# LowLevelv3_1.net
KiCad netlist of a schematic drawn in EAGLE
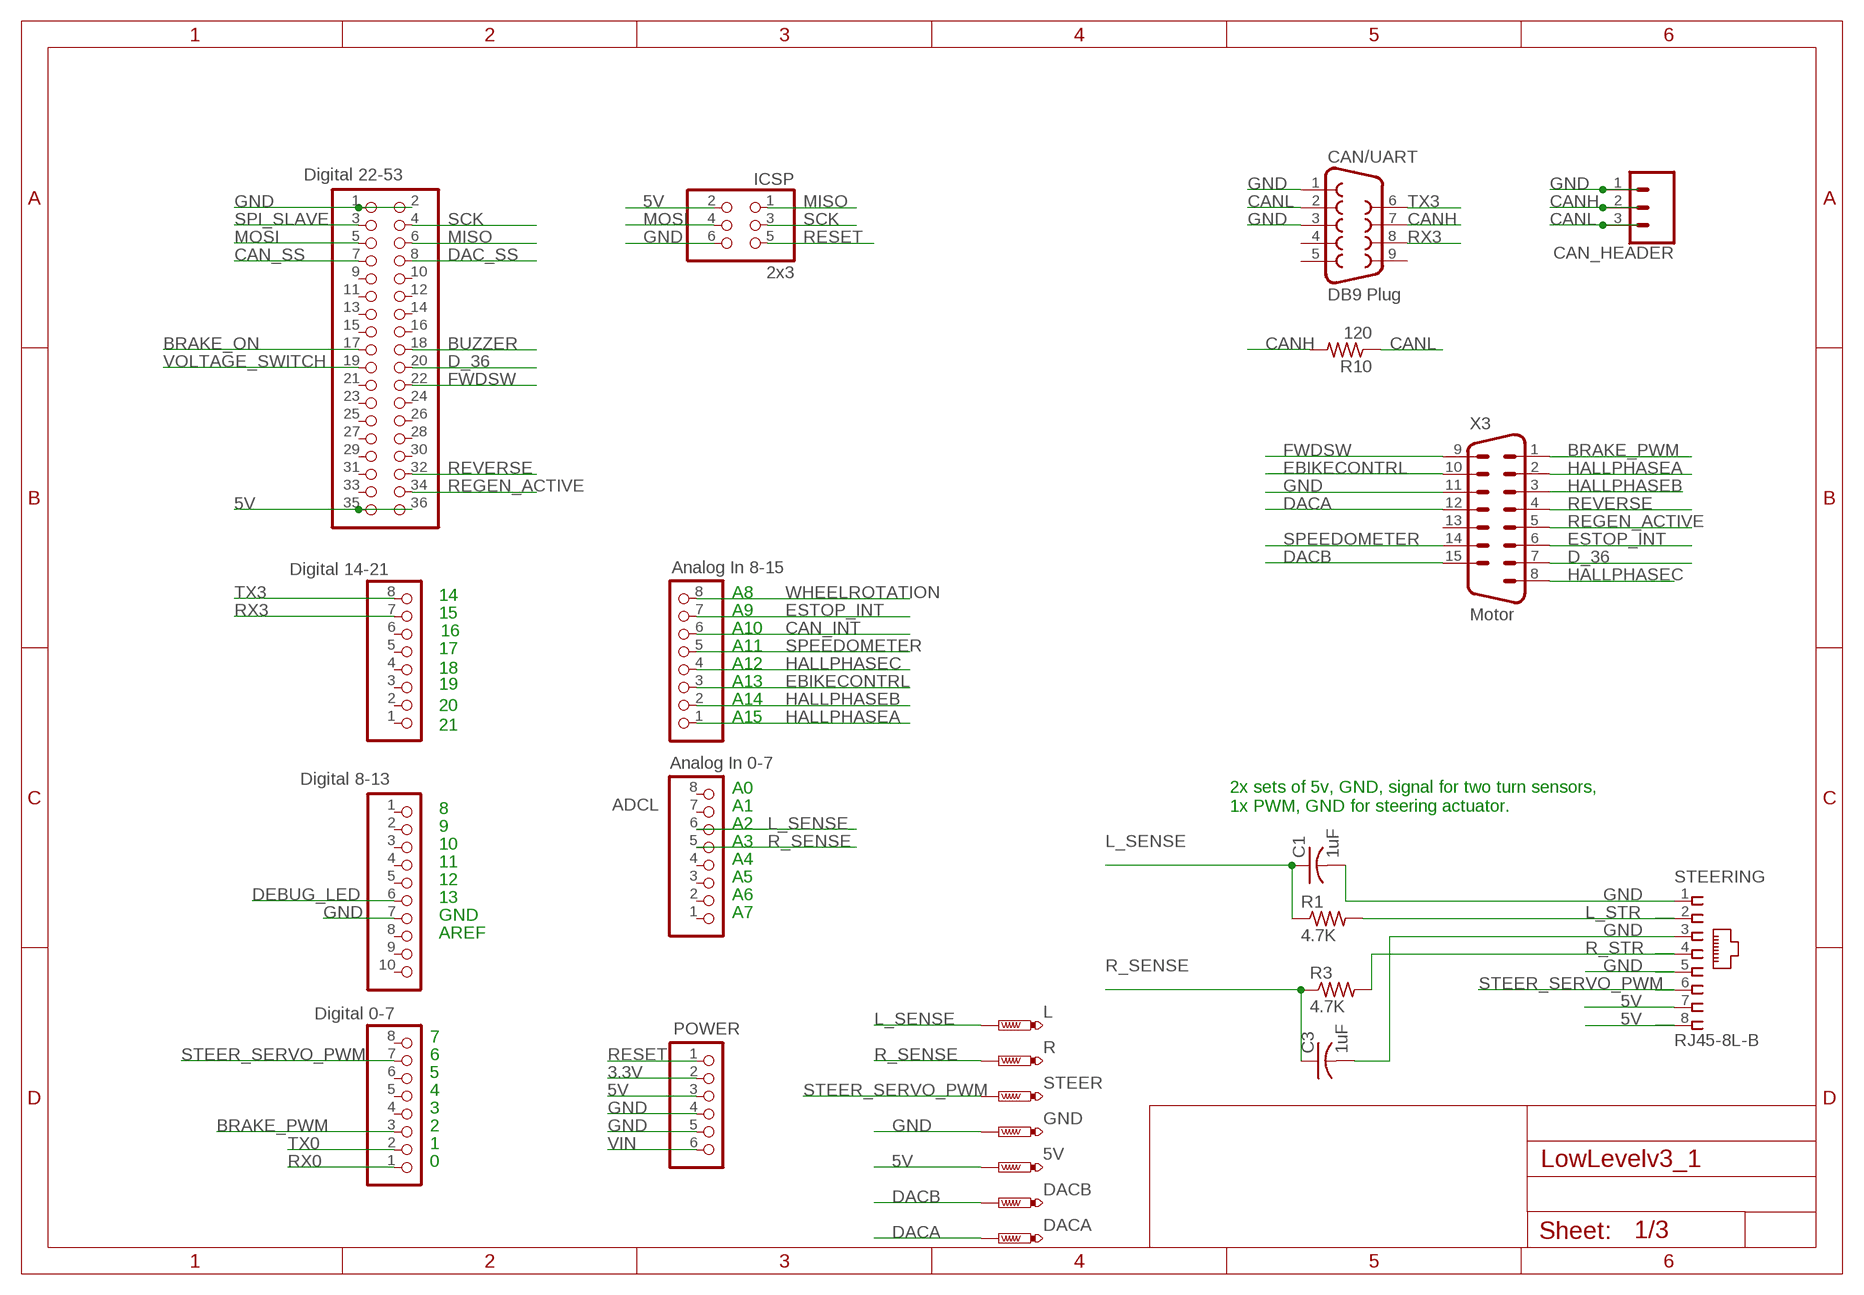
[diagram p0: schematic, sheet 1]
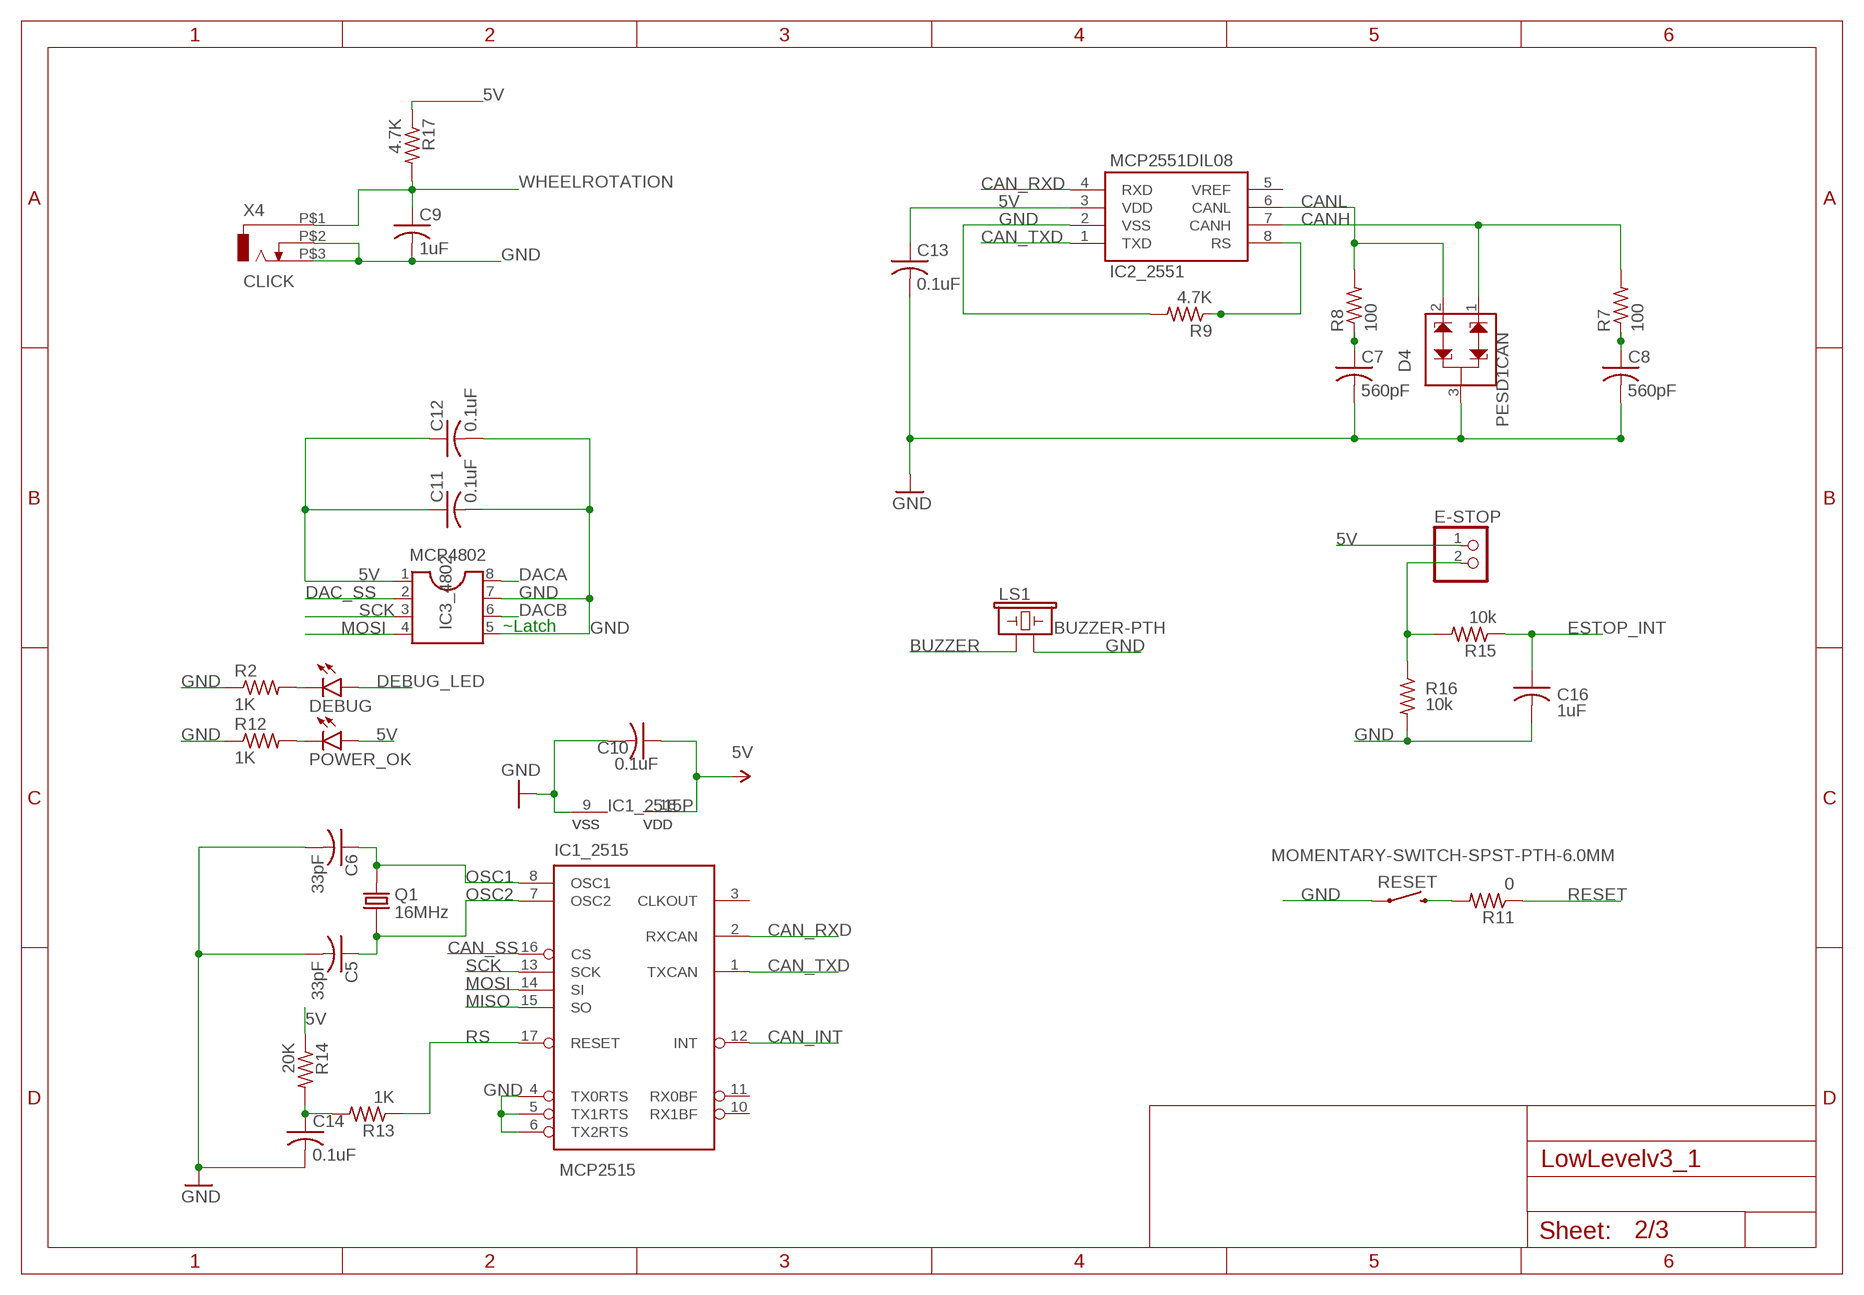
[diagram p1: schematic, sheet 2]
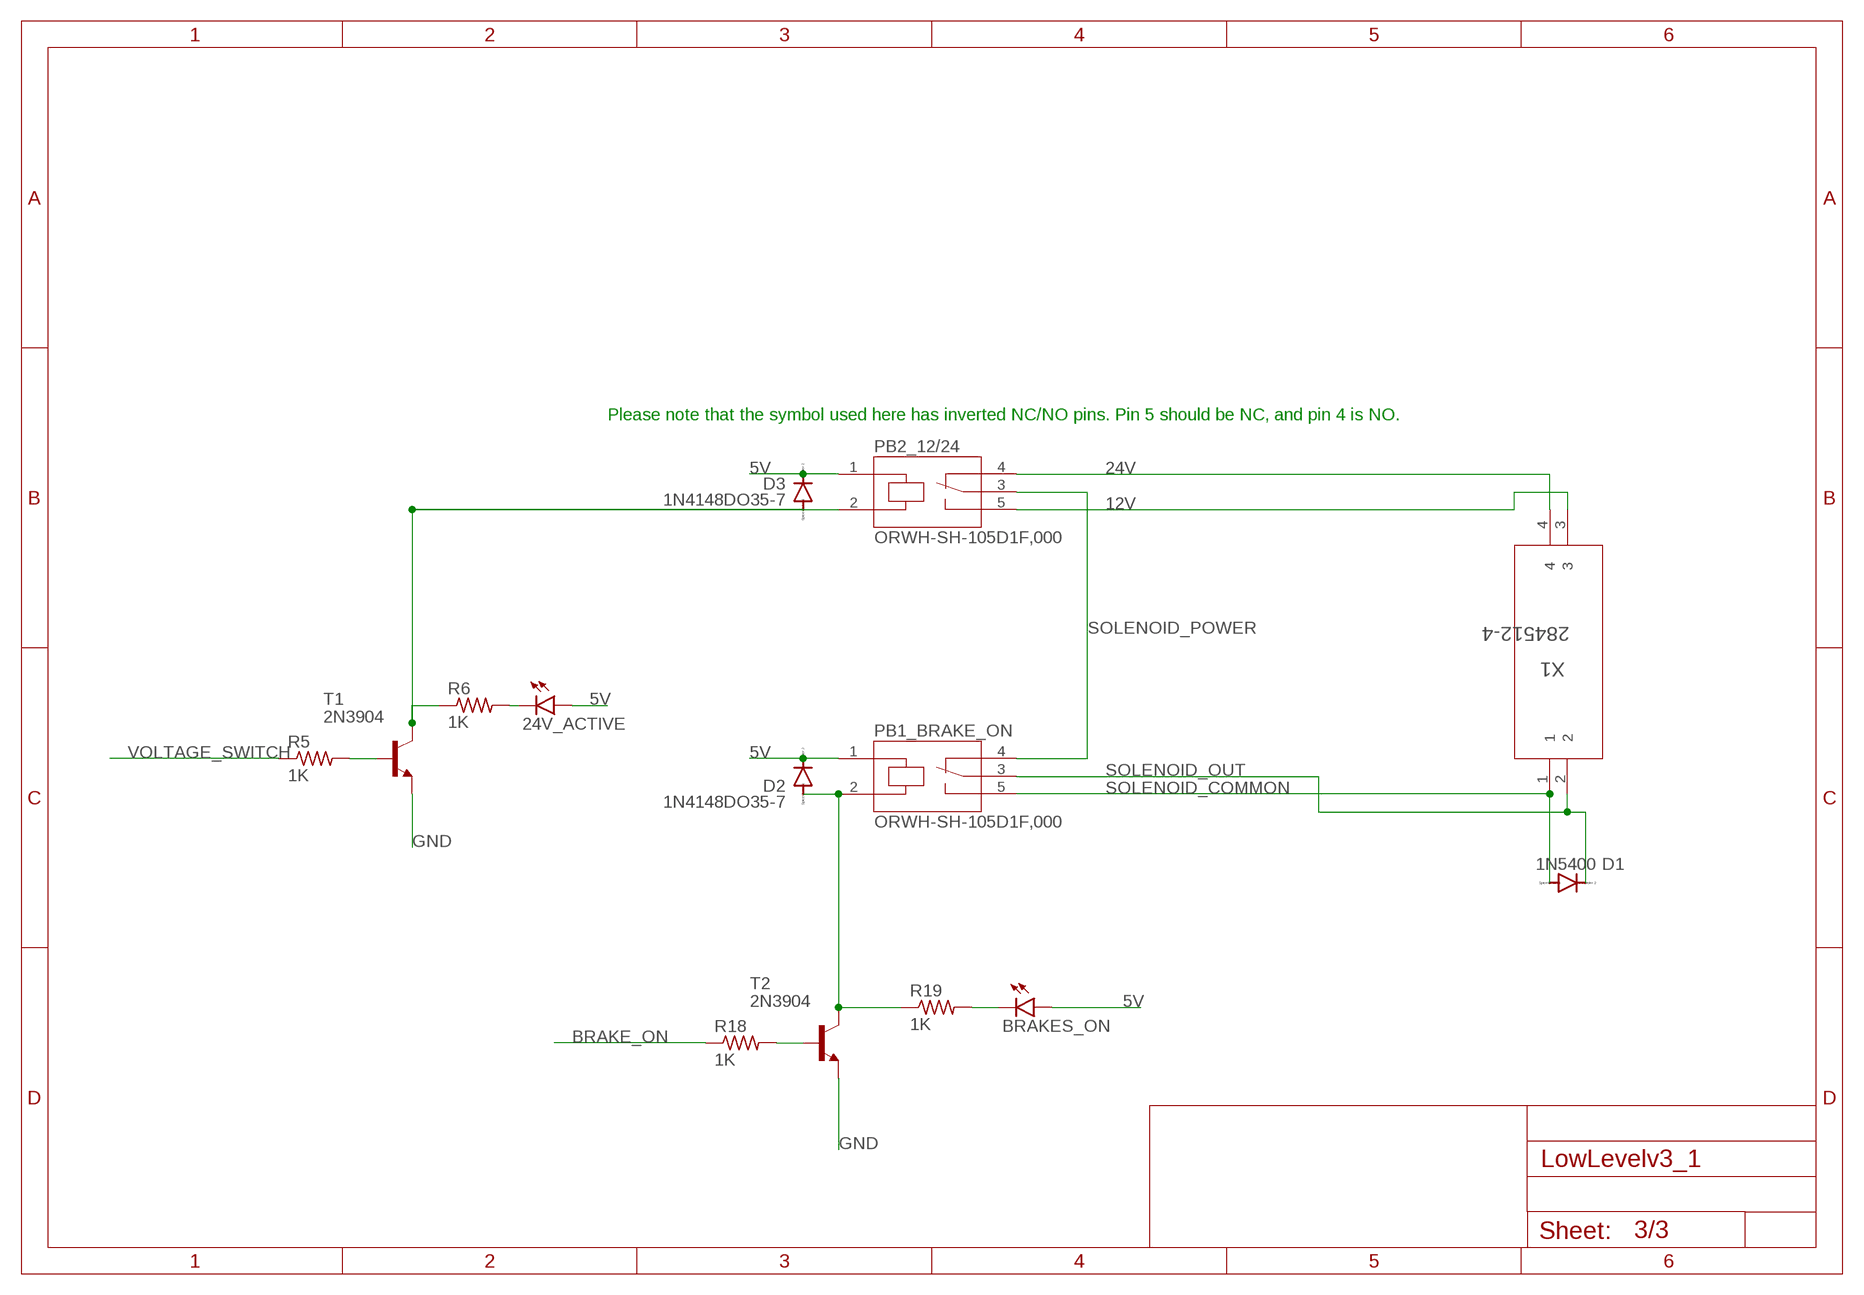
[diagram p2: schematic, sheet 3]

(export (version "E")
  (design (tool "Eeschema 10.0.6"))
  (components
    (comp (ref "5V")
      (value "PTR1PAD1-17")
      (footprint "eagle-import:P1-17")
      (libsource (lib "eagle-import") (part "PTR1PAD1-17"))
    )
    (comp (ref "ADCH")
      (value "Analog In 8-15")
      (footprint "eagle-import:1X08")
      (libsource (lib "eagle-import") (part "PINHD-1X8"))
    )
    (comp (ref "ADCL")
      (value "Analog In 0-7")
      (footprint "eagle-import:1X08")
      (libsource (lib "eagle-import") (part "PINHD-1X8"))
    )
    (comp (ref "C1")
      (value "1uF")
      (footprint "eagle-import:C1206")
      (libsource (lib "eagle-import") (part "C-USC1206"))
    )
    (comp (ref "C3")
      (value "1uF")
      (footprint "eagle-import:C1206")
      (libsource (lib "eagle-import") (part "C-USC1206"))
    )
    (comp (ref "CAN/UART")
      (value "DB9 Plug")
      (footprint "eagle-import:DB9")
      (fields (field (name "SPICEPREFIX") "X"))
      (libsource (lib "eagle-import") (part "DB9FEMALE"))
    )
    (comp (ref "CAN_HEADER")
      (value "CONN_03-SCREW-5MM")
      (footprint "eagle-import:SCREWTERMINAL-5MM-3")
      (libsource (lib "eagle-import") (part "CONN_03-SCREW-5MM"))
    )
    (comp (ref "DACA")
      (value "PTR1PAD1-17")
      (footprint "eagle-import:P1-17")
      (libsource (lib "eagle-import") (part "PTR1PAD1-17"))
    )
    (comp (ref "DACB")
      (value "PTR1PAD1-17")
      (footprint "eagle-import:P1-17")
      (libsource (lib "eagle-import") (part "PTR1PAD1-17"))
    )
    (comp (ref "DIGITAL_0-7")
      (value "Digital 0-7")
      (footprint "eagle-import:1X08")
      (libsource (lib "eagle-import") (part "PINHD-1X8"))
    )
    (comp (ref "DIGITAL_8-13")
      (value "Digital 8-13")
      (footprint "eagle-import:1X10")
      (libsource (lib "eagle-import") (part "PINHD-1X10"))
    )
    (comp (ref "DIGITAL_14-21")
      (value "Digital 14-21")
      (footprint "eagle-import:1X08")
      (libsource (lib "eagle-import") (part "PINHD-1X8"))
    )
    (comp (ref "GND")
      (value "PTR1PAD1-17")
      (footprint "eagle-import:P1-17")
      (libsource (lib "eagle-import") (part "PTR1PAD1-17"))
    )
    (comp (ref "ICSP")
      (value "2x3")
      (footprint "eagle-import:2X03")
      (libsource (lib "eagle-import") (part "PINHD-2X3"))
    )
    (comp (ref "L")
      (value "PTR1PAD1-17")
      (footprint "eagle-import:P1-17")
      (libsource (lib "eagle-import") (part "PTR1PAD1-17"))
    )
    (comp (ref "MEGA_EXPANSION")
      (value "Digital 22-53")
      (footprint "eagle-import:PINHEAD_2X18")
      (libsource (lib "eagle-import") (part "PINHEAD_PINHD-2X18"))
    )
    (comp (ref "POWER")
      (value "PINHD-1X6")
      (footprint "eagle-import:1X06")
      (libsource (lib "eagle-import") (part "PINHD-1X6"))
    )
    (comp (ref "R")
      (value "PTR1PAD1-17")
      (footprint "eagle-import:P1-17")
      (libsource (lib "eagle-import") (part "PTR1PAD1-17"))
    )
    (comp (ref "R1")
      (value "4.7K")
      (footprint "eagle-import:R1206")
      (libsource (lib "eagle-import") (part "R-US_R1206"))
    )
    (comp (ref "R3")
      (value "4.7K")
      (footprint "eagle-import:R1206")
      (libsource (lib "eagle-import") (part "R-US_R1206"))
    )
    (comp (ref "R10")
      (value "120")
      (footprint "eagle-import:R1206")
      (libsource (lib "eagle-import") (part "R-US_R1206"))
    )
    (comp (ref "STEER")
      (value "PTR1PAD1-17")
      (footprint "eagle-import:P1-17")
      (libsource (lib "eagle-import") (part "PTR1PAD1-17"))
    )
    (comp (ref "STEERING")
      (value "RJ45-8L-B")
      (footprint "eagle-import:RJ45-NO-SHIELD")
      (fields (field (name "MF") "TYCO ELECTRONICS"))
      (libsource (lib "eagle-import") (part "RJ45-8L-B"))
    )
    (comp (ref "X3")
      (value "Motor")
      (footprint "eagle-import:182-015-MALE")
      (libsource (lib "eagle-import") (part "M15-182"))
    )
    (comp (ref "24V_ACTIVE")
      (value "LED3MM")
      (footprint "eagle-import:LED3MM")
      (libsource (lib "eagle-import") (part "LED3MM"))
    )
    (comp (ref "BRAKES_ON")
      (value "LED3MM")
      (footprint "eagle-import:LED3MM")
      (libsource (lib "eagle-import") (part "LED3MM"))
    )
    (comp (ref "D1")
      (value "1N5400")
      (footprint "eagle-import:DO201-15")
      (libsource (lib "eagle-import") (part "1N5400"))
    )
    (comp (ref "D2")
      (value "1N4148DO35-7")
      (footprint "eagle-import:DO35-7")
      (libsource (lib "eagle-import") (part "1N4148DO35-7"))
    )
    (comp (ref "D3")
      (value "1N4148DO35-7")
      (footprint "eagle-import:DO35-7")
      (libsource (lib "eagle-import") (part "1N4148DO35-7"))
    )
    (comp (ref "PB1_BRAKE_ON")
      (value "ORWH-SH-105D1F,000")
      (footprint "eagle-import:TE_ORWH-SH-105D1F,000")
      (fields (field (name "DIGI-KEY_PART_NUMBER") "PB2032-ND") (field (name "MF") "TE"))
      (libsource (lib "eagle-import") (part "ORWH-SH-105D1F,000"))
    )
    (comp (ref "PB2_12/24")
      (value "ORWH-SH-105D1F,000")
      (footprint "eagle-import:TE_ORWH-SH-105D1F,000")
      (fields (field (name "DIGI-KEY_PART_NUMBER") "PB2032-ND") (field (name "MF") "TE"))
      (libsource (lib "eagle-import") (part "ORWH-SH-105D1F,000"))
    )
    (comp (ref "R5")
      (value "1K")
      (footprint "eagle-import:R1206")
      (libsource (lib "eagle-import") (part "R-US_R1206"))
    )
    (comp (ref "R6")
      (value "1K")
      (footprint "eagle-import:R1206")
      (libsource (lib "eagle-import") (part "R-US_R1206"))
    )
    (comp (ref "R18")
      (value "1K")
      (footprint "eagle-import:R1206")
      (libsource (lib "eagle-import") (part "R-US_R1206"))
    )
    (comp (ref "R19")
      (value "1K")
      (footprint "eagle-import:R1206")
      (libsource (lib "eagle-import") (part "R-US_R1206"))
    )
    (comp (ref "T1")
      (value "2N3904")
      (footprint "eagle-import:TO92")
      (libsource (lib "eagle-import") (part "2N3904"))
    )
    (comp (ref "T2")
      (value "2N3904")
      (footprint "eagle-import:TO92")
      (libsource (lib "eagle-import") (part "2N3904"))
    )
    (comp (ref "X1")
      (value "284512-4")
      (footprint "eagle-import:284512-4")
      (fields (field (name "MANUFACTURER_PART_NUMBER") "2845124"))
      (libsource (lib "eagle-import") (part "284512-4"))
    )
    (comp (ref "C5")
      (value "33pF")
      (footprint "eagle-import:C1206")
      (libsource (lib "eagle-import") (part "C-USC1206"))
    )
    (comp (ref "C6")
      (value "33pF")
      (footprint "eagle-import:C1206")
      (libsource (lib "eagle-import") (part "C-USC1206"))
    )
    (comp (ref "C7")
      (value "560pF")
      (footprint "eagle-import:C1206")
      (libsource (lib "eagle-import") (part "C-USC1206"))
    )
    (comp (ref "C8")
      (value "560pF")
      (footprint "eagle-import:C1206")
      (libsource (lib "eagle-import") (part "C-USC1206"))
    )
    (comp (ref "C9")
      (value "1uF")
      (footprint "eagle-import:C1206")
      (libsource (lib "eagle-import") (part "C-USC1206"))
    )
    (comp (ref "C10")
      (value "0.1uF")
      (footprint "eagle-import:C1206")
      (libsource (lib "eagle-import") (part "C-USC1206"))
    )
    (comp (ref "C11")
      (value "0.1uF")
      (footprint "eagle-import:C1206")
      (libsource (lib "eagle-import") (part "C-USC1206"))
    )
    (comp (ref "C12")
      (value "0.1uF")
      (footprint "eagle-import:C1206")
      (libsource (lib "eagle-import") (part "C-USC1206"))
    )
    (comp (ref "C13")
      (value "0.1uF")
      (footprint "eagle-import:C1206")
      (libsource (lib "eagle-import") (part "C-USC1206"))
    )
    (comp (ref "C14")
      (value "0.1uF")
      (footprint "eagle-import:C1206")
      (libsource (lib "eagle-import") (part "C-USC1206"))
    )
    (comp (ref "C16")
      (value "1uF")
      (footprint "eagle-import:C1206")
      (libsource (lib "eagle-import") (part "C-USC1206"))
    )
    (comp (ref "D4")
      (value "PESD1CAN")
      (footprint "eagle-import:SPARKFUN-DISCRETESEMI_SOT23-3")
      (fields (field (name "SPICEPREFIX") "J"))
      (libsource (lib "eagle-import") (part "PESD1CAN"))
    )
    (comp (ref "DEBUG")
      (value "LED3MM")
      (footprint "eagle-import:LED3MM")
      (libsource (lib "eagle-import") (part "LED3MM"))
    )
    (comp (ref "E-STOP")
      (value "PINHD-1X2")
      (footprint "eagle-import:1X02")
      (libsource (lib "eagle-import") (part "PINHD-1X2"))
    )
    (comp (ref "IC1_2515")
      (value "MCP2515")
      (footprint "eagle-import:DIP18")
      (fields (field (name "SPICEPREFIX") "X"))
      (libsource (lib "eagle-import") (part "MCP2515(MCP2510)P"))
    )
    (comp (ref "IC2_2551")
      (value "MCP2551DIL08")
      (footprint "eagle-import:IC-PACKAGE_DIL08")
      (fields (field (name "SPICEPREFIX") "X"))
      (libsource (lib "eagle-import") (part "MCP2551DIL08"))
    )
    (comp (ref "IC3_4802")
      (value "MCP4802")
      (footprint "eagle-import:DIL08")
      (libsource (lib "eagle-import") (part "DIL8"))
    )
    (comp (ref "LS1")
      (value "BUZZER-PTH")
      (footprint "eagle-import:BUZZER-12MM")
      (libsource (lib "eagle-import") (part "BUZZER-PTH"))
    )
    (comp (ref "POWER_OK")
      (value "LED3MM")
      (footprint "eagle-import:LED3MM")
      (libsource (lib "eagle-import") (part "LED3MM"))
    )
    (comp (ref "Q1")
      (value "16MHz")
      (footprint "eagle-import:XTAL_ECS-160-20-46X")
      (fields
        (field (name "DIGI-KEY_PART_NUMBER") "XC1759-ND")
        (field (name "MF") "ECS Inc.")
        (field (name "MP") "ECS-160-20-46X")
        (field (name "SPICEPREFIX") "B")
      )
      (libsource (lib "eagle-import") (part "ECS-160-20-46X"))
    )
    (comp (ref "R2")
      (value "1K")
      (footprint "eagle-import:R1206")
      (libsource (lib "eagle-import") (part "R-US_R1206"))
    )
    (comp (ref "R7")
      (value "100")
      (footprint "eagle-import:R1206")
      (libsource (lib "eagle-import") (part "R-US_R1206"))
    )
    (comp (ref "R8")
      (value "100")
      (footprint "eagle-import:R1206")
      (libsource (lib "eagle-import") (part "R-US_R1206"))
    )
    (comp (ref "R9")
      (value "4.7K")
      (footprint "eagle-import:R1206")
      (libsource (lib "eagle-import") (part "R-US_R1206"))
    )
    (comp (ref "R11")
      (value "0")
      (footprint "eagle-import:R1206")
      (libsource (lib "eagle-import") (part "R-US_R1206"))
    )
    (comp (ref "R12")
      (value "1K")
      (footprint "eagle-import:R1206")
      (libsource (lib "eagle-import") (part "R-US_R1206"))
    )
    (comp (ref "R13")
      (value "1K")
      (footprint "eagle-import:R1206")
      (libsource (lib "eagle-import") (part "R-US_R1206"))
    )
    (comp (ref "R14")
      (value "20K")
      (footprint "eagle-import:R1206")
      (libsource (lib "eagle-import") (part "R-US_R1206"))
    )
    (comp (ref "R15")
      (value "10k")
      (footprint "eagle-import:R1206")
      (libsource (lib "eagle-import") (part "R-US_R1206"))
    )
    (comp (ref "R16")
      (value "10k")
      (footprint "eagle-import:R1206")
      (libsource (lib "eagle-import") (part "R-US_R1206"))
    )
    (comp (ref "R17")
      (value "4.7K")
      (footprint "eagle-import:R1206")
      (libsource (lib "eagle-import") (part "R-US_R1206"))
    )
    (comp (ref "RESET")
      (value "MOMENTARY-SWITCH-SPST-PTH-6.0MM")
      (footprint "eagle-import:TACTILE_SWITCH_PTH_6.0MM")
      (libsource (lib "eagle-import") (part "MOMENTARY-SWITCH-SPST-PTH-6.0MM"))
    )
    (comp (ref "X4")
      (value "CLICK")
      (footprint "eagle-import:ODO_JACK")
      (libsource (lib "eagle-import") (part "ODO_JACK"))
    )
  )
  (nets
    (net (code "1") (name "3.3V") (class "Default")
      (node (ref "POWER") (pin "2") (pinfunction "2_2") (pintype "passive"))
    )
    (net (code "2") (name "5V") (class "Default")
      (node (ref "24V_ACTIVE") (pin "A") (pinfunction "A_A") (pintype "passive"))
      (node (ref "5V") (pin "TP") (pinfunction "TP_TP") (pintype "input"))
      (node (ref "BRAKES_ON") (pin "A") (pinfunction "A_A") (pintype "passive"))
      (node (ref "C10") (pin "1") (pinfunction "1_1") (pintype "passive"))
      (node (ref "C11") (pin "1") (pinfunction "1_1") (pintype "passive"))
      (node (ref "C12") (pin "1") (pinfunction "1_1") (pintype "passive"))
      (node (ref "C13") (pin "1") (pinfunction "1_1") (pintype "passive"))
      (node (ref "D2") (pin "C") (pinfunction "C_C") (pintype "passive"))
      (node (ref "D3") (pin "C") (pinfunction "C_C") (pintype "passive"))
      (node (ref "E-STOP") (pin "1") (pinfunction "1_1") (pintype "passive"))
      (node (ref "IC1_2515") (pin "18") (pinfunction "VDD_18") (pintype "power_in"))
      (node (ref "IC2_2551") (pin "3") (pinfunction "VDD_3") (pintype "bidirectional"))
      (node (ref "IC3_4802") (pin "1") (pinfunction "1_1") (pintype "passive"))
      (node (ref "ICSP") (pin "2") (pinfunction "2_2") (pintype "passive"))
      (node (ref "MEGA_EXPANSION") (pin "35") (pinfunction "35_35") (pintype "passive"))
      (node (ref "MEGA_EXPANSION") (pin "36") (pinfunction "36_36") (pintype "passive"))
      (node (ref "PB1_BRAKE_ON") (pin "1") (pinfunction "C1_1") (pintype "passive"))
      (node (ref "PB2_12/24") (pin "1") (pinfunction "C1_1") (pintype "passive"))
      (node (ref "POWER") (pin "3") (pinfunction "3_3") (pintype "passive"))
      (node (ref "POWER_OK") (pin "A") (pinfunction "A_A") (pintype "passive"))
      (node (ref "R14") (pin "1") (pinfunction "1_1") (pintype "passive"))
      (node (ref "R17") (pin "1") (pinfunction "1_1") (pintype "passive"))
      (node (ref "STEERING") (pin "7") (pinfunction "7_7") (pintype "passive"))
      (node (ref "STEERING") (pin "8") (pinfunction "8_8") (pintype "passive"))
    )
    (net (code "3") (name "12V") (class "Default")
      (node (ref "PB2_12/24") (pin "5") (pinfunction "NO_5") (pintype "passive"))
      (node (ref "X1") (pin "3") (pinfunction "3_3") (pintype "passive"))
    )
    (net (code "4") (name "24V") (class "Default")
      (node (ref "PB2_12/24") (pin "4") (pinfunction "NC_4") (pintype "passive"))
      (node (ref "X1") (pin "4") (pinfunction "4_4") (pintype "passive"))
    )
    (net (code "5") (name "BRAKE_ON") (class "Default")
      (node (ref "MEGA_EXPANSION") (pin "17") (pinfunction "17_17") (pintype "passive"))
      (node (ref "R18") (pin "1") (pinfunction "1_1") (pintype "passive"))
    )
    (net (code "6") (name "BRAKE_PWM") (class "Default")
      (node (ref "DIGITAL_0-7") (pin "3") (pinfunction "3_3") (pintype "passive"))
      (node (ref "X3") (pin "1") (pinfunction "1_1") (pintype "passive"))
    )
    (net (code "7") (name "BUZZER") (class "Default")
      (node (ref "LS1") (pin "+") (pinfunction "1_+") (pintype "passive"))
      (node (ref "MEGA_EXPANSION") (pin "18") (pinfunction "18_18") (pintype "passive"))
    )
    (net (code "8") (name "CANH") (class "Default")
      (node (ref "CAN/UART") (pin "7") (pinfunction "7_7") (pintype "passive"))
      (node (ref "CAN_HEADER") (pin "2") (pinfunction "2_2") (pintype "passive"))
      (node (ref "D4") (pin "1") (pinfunction "1_1") (pintype "bidirectional"))
      (node (ref "IC2_2551") (pin "7") (pinfunction "CANH_7") (pintype "bidirectional"))
      (node (ref "R10") (pin "2") (pinfunction "2_2") (pintype "passive"))
      (node (ref "R7") (pin "2") (pinfunction "2_2") (pintype "passive"))
    )
    (net (code "9") (name "CANL") (class "Default")
      (node (ref "CAN/UART") (pin "2") (pinfunction "2_2") (pintype "passive"))
      (node (ref "CAN_HEADER") (pin "3") (pinfunction "3_3") (pintype "passive"))
      (node (ref "D4") (pin "2") (pinfunction "2_2") (pintype "bidirectional"))
      (node (ref "IC2_2551") (pin "6") (pinfunction "CANL_6") (pintype "bidirectional"))
      (node (ref "R10") (pin "1") (pinfunction "1_1") (pintype "passive"))
      (node (ref "R8") (pin "2") (pinfunction "2_2") (pintype "passive"))
    )
    (net (code "10") (name "CAN_INT") (class "Default")
      (node (ref "ADCH") (pin "6") (pinfunction "6_6") (pintype "passive"))
      (node (ref "IC1_2515") (pin "12") (pinfunction "INT_12") (pintype "output"))
    )
    (net (code "11") (name "CAN_RXD") (class "Default")
      (node (ref "IC1_2515") (pin "2") (pinfunction "RXCAN_2") (pintype "input"))
      (node (ref "IC2_2551") (pin "4") (pinfunction "RXD_4") (pintype "bidirectional"))
    )
    (net (code "12") (name "CAN_SS") (class "Default")
      (node (ref "IC1_2515") (pin "16") (pinfunction "CS_16") (pintype "input"))
      (node (ref "MEGA_EXPANSION") (pin "7") (pinfunction "7_7") (pintype "passive"))
    )
    (net (code "13") (name "CAN_TXD") (class "Default")
      (node (ref "IC1_2515") (pin "1") (pinfunction "TXCAN_1") (pintype "output"))
      (node (ref "IC2_2551") (pin "1") (pinfunction "TXD_1") (pintype "bidirectional"))
    )
    (net (code "14") (name "DACA") (class "Default")
      (node (ref "DACA") (pin "TP") (pinfunction "TP_TP") (pintype "input"))
      (node (ref "IC3_4802") (pin "8") (pinfunction "8_8") (pintype "passive"))
      (node (ref "X3") (pin "12") (pinfunction "12_12") (pintype "passive"))
    )
    (net (code "15") (name "DACB") (class "Default")
      (node (ref "DACB") (pin "TP") (pinfunction "TP_TP") (pintype "input"))
      (node (ref "IC3_4802") (pin "6") (pinfunction "6_6") (pintype "passive"))
      (node (ref "X3") (pin "15") (pinfunction "15_15") (pintype "passive"))
    )
    (net (code "16") (name "DAC_SS") (class "Default")
      (node (ref "IC3_4802") (pin "2") (pinfunction "2_2") (pintype "passive"))
      (node (ref "MEGA_EXPANSION") (pin "8") (pinfunction "8_8") (pintype "passive"))
    )
    (net (code "17") (name "DEBUG_LED") (class "Default")
      (node (ref "DEBUG") (pin "A") (pinfunction "A_A") (pintype "passive"))
      (node (ref "DIGITAL_8-13") (pin "6") (pinfunction "6_6") (pintype "passive"))
    )
    (net (code "18") (name "D_36") (class "Default")
      (node (ref "MEGA_EXPANSION") (pin "20") (pinfunction "20_20") (pintype "passive"))
      (node (ref "X3") (pin "7") (pinfunction "7_7") (pintype "passive"))
    )
    (net (code "19") (name "EBIKECONTRL") (class "Default")
      (node (ref "ADCH") (pin "3") (pinfunction "3_3") (pintype "passive"))
      (node (ref "X3") (pin "10") (pinfunction "10_10") (pintype "passive"))
    )
    (net (code "20") (name "ESTOP_INT") (class "Default")
      (node (ref "ADCH") (pin "7") (pinfunction "7_7") (pintype "passive"))
      (node (ref "C16") (pin "1") (pinfunction "1_1") (pintype "passive"))
      (node (ref "R15") (pin "1") (pinfunction "1_1") (pintype "passive"))
      (node (ref "X3") (pin "6") (pinfunction "6_6") (pintype "passive"))
    )
    (net (code "21") (name "FWDSW") (class "Default")
      (node (ref "MEGA_EXPANSION") (pin "22") (pinfunction "22_22") (pintype "passive"))
      (node (ref "X3") (pin "9") (pinfunction "9_9") (pintype "passive"))
    )
    (net (code "22") (name "GND") (class "Default")
      (node (ref "C1") (pin "2") (pinfunction "2_2") (pintype "passive"))
      (node (ref "C10") (pin "2") (pinfunction "2_2") (pintype "passive"))
      (node (ref "C11") (pin "2") (pinfunction "2_2") (pintype "passive"))
      (node (ref "C12") (pin "2") (pinfunction "2_2") (pintype "passive"))
      (node (ref "C13") (pin "2") (pinfunction "2_2") (pintype "passive"))
      (node (ref "C14") (pin "2") (pinfunction "2_2") (pintype "passive"))
      (node (ref "C16") (pin "2") (pinfunction "2_2") (pintype "passive"))
      (node (ref "C3") (pin "2") (pinfunction "2_2") (pintype "passive"))
      (node (ref "C5") (pin "2") (pinfunction "2_2") (pintype "passive"))
      (node (ref "C6") (pin "2") (pinfunction "2_2") (pintype "passive"))
      (node (ref "C7") (pin "2") (pinfunction "2_2") (pintype "passive"))
      (node (ref "C8") (pin "2") (pinfunction "2_2") (pintype "passive"))
      (node (ref "C9") (pin "2") (pinfunction "2_2") (pintype "passive"))
      (node (ref "CAN/UART") (pin "1") (pinfunction "1_1") (pintype "passive"))
      (node (ref "CAN/UART") (pin "3") (pinfunction "3_3") (pintype "passive"))
      (node (ref "CAN_HEADER") (pin "1") (pinfunction "1_1") (pintype "passive"))
      (node (ref "D4") (pin "3") (pinfunction "3_3") (pintype "bidirectional"))
      (node (ref "DIGITAL_8-13") (pin "7") (pinfunction "7_7") (pintype "passive"))
      (node (ref "GND") (pin "TP") (pinfunction "TP_TP") (pintype "input"))
      (node (ref "IC1_2515") (pin "4") (pinfunction "TX0RTS_4") (pintype "input"))
      (node (ref "IC1_2515") (pin "5") (pinfunction "TX1RTS_5") (pintype "input"))
      (node (ref "IC1_2515") (pin "6") (pinfunction "TX2RTS_6") (pintype "input"))
      (node (ref "IC1_2515") (pin "9") (pinfunction "VSS_9") (pintype "power_in"))
      (node (ref "IC2_2551") (pin "2") (pinfunction "VSS_2") (pintype "bidirectional"))
      (node (ref "IC3_4802") (pin "5") (pinfunction "5_5") (pintype "passive"))
      (node (ref "IC3_4802") (pin "7") (pinfunction "7_7") (pintype "passive"))
      (node (ref "ICSP") (pin "6") (pinfunction "6_6") (pintype "passive"))
      (node (ref "LS1") (pin "-") (pinfunction "2_-") (pintype "passive"))
      (node (ref "MEGA_EXPANSION") (pin "1") (pinfunction "1_1") (pintype "passive"))
      (node (ref "MEGA_EXPANSION") (pin "2") (pinfunction "2_2") (pintype "passive"))
      (node (ref "POWER") (pin "4") (pinfunction "4_4") (pintype "passive"))
      (node (ref "POWER") (pin "5") (pinfunction "5_5") (pintype "passive"))
      (node (ref "R12") (pin "1") (pinfunction "1_1") (pintype "passive"))
      (node (ref "R16") (pin "2") (pinfunction "2_2") (pintype "passive"))
      (node (ref "R2") (pin "1") (pinfunction "1_1") (pintype "passive"))
      (node (ref "R9") (pin "2") (pinfunction "2_2") (pintype "passive"))
      (node (ref "RESET") (pin "1") (pinfunction "1_1") (pintype "passive"))
      (node (ref "STEERING") (pin "1") (pinfunction "1_1") (pintype "passive"))
      (node (ref "STEERING") (pin "3") (pinfunction "3_3") (pintype "passive"))
      (node (ref "STEERING") (pin "5") (pinfunction "5_5") (pintype "passive"))
      (node (ref "T1") (pin "3") (pinfunction "E_3") (pintype "passive"))
      (node (ref "T2") (pin "3") (pinfunction "E_3") (pintype "passive"))
      (node (ref "X3") (pin "11") (pinfunction "11_11") (pintype "passive"))
      (node (ref "X4") (pin "P$2") (pinfunction "2_P$2") (pintype "passive"))
      (node (ref "X4") (pin "P$3") (pinfunction "3_P$3") (pintype "passive"))
    )
    (net (code "23") (name "HALLPHASEA") (class "Default")
      (node (ref "ADCH") (pin "1") (pinfunction "1_1") (pintype "passive"))
      (node (ref "X3") (pin "2") (pinfunction "2_2") (pintype "passive"))
    )
    (net (code "24") (name "HALLPHASEB") (class "Default")
      (node (ref "ADCH") (pin "2") (pinfunction "2_2") (pintype "passive"))
      (node (ref "X3") (pin "3") (pinfunction "3_3") (pintype "passive"))
    )
    (net (code "25") (name "HALLPHASEC") (class "Default")
      (node (ref "ADCH") (pin "4") (pinfunction "4_4") (pintype "passive"))
      (node (ref "X3") (pin "8") (pinfunction "8_8") (pintype "passive"))
    )
    (net (code "26") (name "L_SENSE") (class "Default")
      (node (ref "ADCL") (pin "6") (pinfunction "6_6") (pintype "passive"))
      (node (ref "C1") (pin "1") (pinfunction "1_1") (pintype "passive"))
      (node (ref "L") (pin "TP") (pinfunction "TP_TP") (pintype "input"))
      (node (ref "R1") (pin "1") (pinfunction "1_1") (pintype "passive"))
    )
    (net (code "27") (name "L_STR") (class "Default")
      (node (ref "R1") (pin "2") (pinfunction "2_2") (pintype "passive"))
      (node (ref "STEERING") (pin "2") (pinfunction "2_2") (pintype "passive"))
    )
    (net (code "28") (name "MISO") (class "Default")
      (node (ref "IC1_2515") (pin "15") (pinfunction "SO_15") (pintype "output"))
      (node (ref "ICSP") (pin "1") (pinfunction "1_1") (pintype "passive"))
      (node (ref "MEGA_EXPANSION") (pin "6") (pinfunction "6_6") (pintype "passive"))
    )
    (net (code "29") (name "MOSI") (class "Default")
      (node (ref "IC1_2515") (pin "14") (pinfunction "SI_14") (pintype "input"))
      (node (ref "IC3_4802") (pin "4") (pinfunction "4_4") (pintype "passive"))
      (node (ref "ICSP") (pin "4") (pinfunction "4_4") (pintype "passive"))
      (node (ref "MEGA_EXPANSION") (pin "5") (pinfunction "5_5") (pintype "passive"))
    )
    (net (code "30") (name "Net-(24V_ACTIVE-C)") (class "Default")
      (node (ref "24V_ACTIVE") (pin "K") (pinfunction "C_K") (pintype "passive"))
      (node (ref "R6") (pin "2") (pinfunction "2_2") (pintype "passive"))
    )
    (net (code "31") (name "Net-(BRAKES_ON-C)") (class "Default")
      (node (ref "BRAKES_ON") (pin "K") (pinfunction "C_K") (pintype "passive"))
      (node (ref "R19") (pin "2") (pinfunction "2_2") (pintype "passive"))
    )
    (net (code "32") (name "Net-(C7-Pad1)") (class "Default")
      (node (ref "C7") (pin "1") (pinfunction "1_1") (pintype "passive"))
      (node (ref "R8") (pin "1") (pinfunction "1_1") (pintype "passive"))
    )
    (net (code "33") (name "Net-(C8-Pad1)") (class "Default")
      (node (ref "C8") (pin "1") (pinfunction "1_1") (pintype "passive"))
      (node (ref "R7") (pin "1") (pinfunction "1_1") (pintype "passive"))
    )
    (net (code "34") (name "Net-(C14-Pad1)") (class "Default")
      (node (ref "C14") (pin "1") (pinfunction "1_1") (pintype "passive"))
      (node (ref "R13") (pin "2") (pinfunction "2_2") (pintype "passive"))
      (node (ref "R14") (pin "2") (pinfunction "2_2") (pintype "passive"))
    )
    (net (code "35") (name "Net-(DEBUG-C)") (class "Default")
      (node (ref "DEBUG") (pin "K") (pinfunction "C_K") (pintype "passive"))
      (node (ref "R2") (pin "2") (pinfunction "2_2") (pintype "passive"))
    )
    (net (code "36") (name "Net-(E-STOP-Pad2)") (class "Default")
      (node (ref "E-STOP") (pin "2") (pinfunction "2_2") (pintype "passive"))
      (node (ref "R15") (pin "2") (pinfunction "2_2") (pintype "passive"))
      (node (ref "R16") (pin "1") (pinfunction "1_1") (pintype "passive"))
    )
    (net (code "37") (name "Net-(IC2_2551-RS)") (class "Default")
      (node (ref "IC2_2551") (pin "8") (pinfunction "RS_8") (pintype "bidirectional"))
      (node (ref "R9") (pin "1") (pinfunction "1_1") (pintype "passive"))
    )
    (net (code "38") (name "Net-(PB1_BRAKE_ON-C2)") (class "Default")
      (node (ref "D2") (pin "A") (pinfunction "A_A") (pintype "passive"))
      (node (ref "PB1_BRAKE_ON") (pin "2") (pinfunction "C2_2") (pintype "passive"))
      (node (ref "R19") (pin "1") (pinfunction "1_1") (pintype "passive"))
      (node (ref "T2") (pin "1") (pinfunction "C_1") (pintype "passive"))
    )
    (net (code "39") (name "Net-(PB2_12/24-C2)") (class "Default")
      (node (ref "D3") (pin "A") (pinfunction "A_A") (pintype "passive"))
      (node (ref "PB2_12/24") (pin "2") (pinfunction "C2_2") (pintype "passive"))
      (node (ref "R6") (pin "1") (pinfunction "1_1") (pintype "passive"))
      (node (ref "T1") (pin "1") (pinfunction "C_1") (pintype "passive"))
    )
    (net (code "40") (name "Net-(POWER_OK-C)") (class "Default")
      (node (ref "POWER_OK") (pin "K") (pinfunction "C_K") (pintype "passive"))
      (node (ref "R12") (pin "2") (pinfunction "2_2") (pintype "passive"))
    )
    (net (code "41") (name "Net-(RESET-2)") (class "Default")
      (node (ref "R11") (pin "2") (pinfunction "2_2") (pintype "passive"))
      (node (ref "RESET") (pin "3") (pinfunction "2_3") (pintype "passive"))
    )
    (net (code "42") (name "Net-(T1-B)") (class "Default")
      (node (ref "R5") (pin "2") (pinfunction "2_2") (pintype "passive"))
      (node (ref "T1") (pin "2") (pinfunction "B_2") (pintype "passive"))
    )
    (net (code "43") (name "Net-(T2-B)") (class "Default")
      (node (ref "R18") (pin "2") (pinfunction "2_2") (pintype "passive"))
      (node (ref "T2") (pin "2") (pinfunction "B_2") (pintype "passive"))
    )
    (net (code "44") (name "OSC1") (class "Default")
      (node (ref "C6") (pin "1") (pinfunction "1_1") (pintype "passive"))
      (node (ref "IC1_2515") (pin "8") (pinfunction "OSC1_8") (pintype "input"))
      (node (ref "Q1") (pin "2") (pinfunction "2_2") (pintype "passive"))
    )
    (net (code "45") (name "OSC2") (class "Default")
      (node (ref "C5") (pin "1") (pinfunction "1_1") (pintype "passive"))
      (node (ref "IC1_2515") (pin "7") (pinfunction "OSC2_7") (pintype "output"))
      (node (ref "Q1") (pin "1") (pinfunction "1_1") (pintype "passive"))
    )
    (net (code "46") (name "REGEN_ACTIVE") (class "Default")
      (node (ref "MEGA_EXPANSION") (pin "34") (pinfunction "34_34") (pintype "passive"))
      (node (ref "X3") (pin "5") (pinfunction "5_5") (pintype "passive"))
    )
    (net (code "47") (name "RESET") (class "Default")
      (node (ref "ICSP") (pin "5") (pinfunction "5_5") (pintype "passive"))
      (node (ref "POWER") (pin "1") (pinfunction "1_1") (pintype "passive"))
      (node (ref "R11") (pin "1") (pinfunction "1_1") (pintype "passive"))
    )
    (net (code "48") (name "REVERSE") (class "Default")
      (node (ref "MEGA_EXPANSION") (pin "32") (pinfunction "32_32") (pintype "passive"))
      (node (ref "X3") (pin "4") (pinfunction "4_4") (pintype "passive"))
    )
    (net (code "49") (name "RS") (class "Default")
      (node (ref "IC1_2515") (pin "17") (pinfunction "RESET_17") (pintype "input"))
      (node (ref "R13") (pin "1") (pinfunction "1_1") (pintype "passive"))
    )
    (net (code "50") (name "RX0") (class "Default")
      (node (ref "DIGITAL_0-7") (pin "1") (pinfunction "1_1") (pintype "passive"))
    )
    (net (code "51") (name "RX3") (class "Default")
      (node (ref "CAN/UART") (pin "8") (pinfunction "8_8") (pintype "passive"))
      (node (ref "DIGITAL_14-21") (pin "7") (pinfunction "7_7") (pintype "passive"))
    )
    (net (code "52") (name "R_SENSE") (class "Default")
      (node (ref "ADCL") (pin "5") (pinfunction "5_5") (pintype "passive"))
      (node (ref "C3") (pin "1") (pinfunction "1_1") (pintype "passive"))
      (node (ref "R") (pin "TP") (pinfunction "TP_TP") (pintype "input"))
      (node (ref "R3") (pin "1") (pinfunction "1_1") (pintype "passive"))
    )
    (net (code "53") (name "R_STR") (class "Default")
      (node (ref "R3") (pin "2") (pinfunction "2_2") (pintype "passive"))
      (node (ref "STEERING") (pin "4") (pinfunction "4_4") (pintype "passive"))
    )
    (net (code "54") (name "SCK") (class "Default")
      (node (ref "IC1_2515") (pin "13") (pinfunction "SCK_13") (pintype "input"))
      (node (ref "IC3_4802") (pin "3") (pinfunction "3_3") (pintype "passive"))
      (node (ref "ICSP") (pin "3") (pinfunction "3_3") (pintype "passive"))
      (node (ref "MEGA_EXPANSION") (pin "4") (pinfunction "4_4") (pintype "passive"))
    )
    (net (code "55") (name "SOLENOID_COMMON") (class "Default")
      (node (ref "D1") (pin "A") (pinfunction "A_A") (pintype "passive"))
      (node (ref "PB1_BRAKE_ON") (pin "5") (pinfunction "NO_5") (pintype "passive"))
      (node (ref "X1") (pin "1") (pinfunction "1_1") (pintype "passive"))
    )
    (net (code "56") (name "SOLENOID_OUT") (class "Default")
      (node (ref "D1") (pin "C") (pinfunction "C_C") (pintype "passive"))
      (node (ref "PB1_BRAKE_ON") (pin "3") (pinfunction "C_3") (pintype "passive"))
      (node (ref "X1") (pin "2") (pinfunction "2_2") (pintype "passive"))
    )
    (net (code "57") (name "SOLENOID_POWER") (class "Default")
      (node (ref "PB1_BRAKE_ON") (pin "4") (pinfunction "NC_4") (pintype "passive"))
      (node (ref "PB2_12/24") (pin "3") (pinfunction "C_3") (pintype "passive"))
    )
    (net (code "58") (name "SPEEDOMETER") (class "Default")
      (node (ref "ADCH") (pin "5") (pinfunction "5_5") (pintype "passive"))
      (node (ref "X3") (pin "14") (pinfunction "14_14") (pintype "passive"))
    )
    (net (code "59") (name "SPI_SLAVE") (class "Default")
      (node (ref "MEGA_EXPANSION") (pin "3") (pinfunction "3_3") (pintype "passive"))
    )
    (net (code "60") (name "STEER_SERVO_PWM") (class "Default")
      (node (ref "DIGITAL_0-7") (pin "7") (pinfunction "7_7") (pintype "passive"))
      (node (ref "STEER") (pin "TP") (pinfunction "TP_TP") (pintype "input"))
      (node (ref "STEERING") (pin "6") (pinfunction "6_6") (pintype "passive"))
    )
    (net (code "61") (name "TX0") (class "Default")
      (node (ref "DIGITAL_0-7") (pin "2") (pinfunction "2_2") (pintype "passive"))
    )
    (net (code "62") (name "TX3") (class "Default")
      (node (ref "CAN/UART") (pin "6") (pinfunction "6_6") (pintype "passive"))
      (node (ref "DIGITAL_14-21") (pin "8") (pinfunction "8_8") (pintype "passive"))
    )
    (net (code "63") (name "VIN") (class "Default")
      (node (ref "POWER") (pin "6") (pinfunction "6_6") (pintype "passive"))
    )
    (net (code "64") (name "VOLTAGE_SWITCH") (class "Default")
      (node (ref "MEGA_EXPANSION") (pin "19") (pinfunction "19_19") (pintype "passive"))
      (node (ref "R5") (pin "1") (pinfunction "1_1") (pintype "passive"))
    )
    (net (code "65") (name "WHEELROTATION") (class "Default")
      (node (ref "ADCH") (pin "8") (pinfunction "8_8") (pintype "passive"))
      (node (ref "C9") (pin "1") (pinfunction "1_1") (pintype "passive"))
      (node (ref "R17") (pin "2") (pinfunction "2_2") (pintype "passive"))
      (node (ref "X4") (pin "P$1") (pinfunction "1_P$1") (pintype "passive"))
    )
    (net (code "66") (name "unconnected-(ADCL-Pad1)") (class "Default")
      (node (ref "ADCL") (pin "1") (pinfunction "1_1") (pintype "passive"))
    )
    (net (code "67") (name "unconnected-(ADCL-Pad2)") (class "Default")
      (node (ref "ADCL") (pin "2") (pinfunction "2_2") (pintype "passive"))
    )
    (net (code "68") (name "unconnected-(ADCL-Pad3)") (class "Default")
      (node (ref "ADCL") (pin "3") (pinfunction "3_3") (pintype "passive"))
    )
    (net (code "69") (name "unconnected-(ADCL-Pad4)") (class "Default")
      (node (ref "ADCL") (pin "4") (pinfunction "4_4") (pintype "passive"))
    )
    (net (code "70") (name "unconnected-(ADCL-Pad7)") (class "Default")
      (node (ref "ADCL") (pin "7") (pinfunction "7_7") (pintype "passive"))
    )
    (net (code "71") (name "unconnected-(ADCL-Pad8)") (class "Default")
      (node (ref "ADCL") (pin "8") (pinfunction "8_8") (pintype "passive"))
    )
    (net (code "72") (name "unconnected-(CAN/UART-Pad4)") (class "Default")
      (node (ref "CAN/UART") (pin "4") (pinfunction "4_4") (pintype "passive"))
    )
    (net (code "73") (name "unconnected-(CAN/UART-Pad5)") (class "Default")
      (node (ref "CAN/UART") (pin "5") (pinfunction "5_5") (pintype "passive"))
    )
    (net (code "74") (name "unconnected-(CAN/UART-Pad9)") (class "Default")
      (node (ref "CAN/UART") (pin "9") (pinfunction "9_9") (pintype "passive"))
    )
    (net (code "75") (name "unconnected-(DIGITAL_0-7-Pad4)") (class "Default")
      (node (ref "DIGITAL_0-7") (pin "4") (pinfunction "4_4") (pintype "passive"))
    )
    (net (code "76") (name "unconnected-(DIGITAL_0-7-Pad5)") (class "Default")
      (node (ref "DIGITAL_0-7") (pin "5") (pinfunction "5_5") (pintype "passive"))
    )
    (net (code "77") (name "unconnected-(DIGITAL_0-7-Pad6)") (class "Default")
      (node (ref "DIGITAL_0-7") (pin "6") (pinfunction "6_6") (pintype "passive"))
    )
    (net (code "78") (name "unconnected-(DIGITAL_0-7-Pad8)") (class "Default")
      (node (ref "DIGITAL_0-7") (pin "8") (pinfunction "8_8") (pintype "passive"))
    )
    (net (code "79") (name "unconnected-(DIGITAL_8-13-Pad1)") (class "Default")
      (node (ref "DIGITAL_8-13") (pin "1") (pinfunction "1_1") (pintype "passive"))
    )
    (net (code "80") (name "unconnected-(DIGITAL_8-13-Pad2)") (class "Default")
      (node (ref "DIGITAL_8-13") (pin "2") (pinfunction "2_2") (pintype "passive"))
    )
    (net (code "81") (name "unconnected-(DIGITAL_8-13-Pad3)") (class "Default")
      (node (ref "DIGITAL_8-13") (pin "3") (pinfunction "3_3") (pintype "passive"))
    )
    (net (code "82") (name "unconnected-(DIGITAL_8-13-Pad4)") (class "Default")
      (node (ref "DIGITAL_8-13") (pin "4") (pinfunction "4_4") (pintype "passive"))
    )
    (net (code "83") (name "unconnected-(DIGITAL_8-13-Pad5)") (class "Default")
      (node (ref "DIGITAL_8-13") (pin "5") (pinfunction "5_5") (pintype "passive"))
    )
    (net (code "84") (name "unconnected-(DIGITAL_8-13-Pad8)") (class "Default")
      (node (ref "DIGITAL_8-13") (pin "8") (pinfunction "8_8") (pintype "passive"))
    )
    (net (code "85") (name "unconnected-(DIGITAL_8-13-Pad9)") (class "Default")
      (node (ref "DIGITAL_8-13") (pin "9") (pinfunction "9_9") (pintype "passive"))
    )
    (net (code "86") (name "unconnected-(DIGITAL_8-13-Pad10)") (class "Default")
      (node (ref "DIGITAL_8-13") (pin "10") (pinfunction "10_10") (pintype "passive"))
    )
    (net (code "87") (name "unconnected-(DIGITAL_14-21-Pad1)") (class "Default")
      (node (ref "DIGITAL_14-21") (pin "1") (pinfunction "1_1") (pintype "passive"))
    )
    (net (code "88") (name "unconnected-(DIGITAL_14-21-Pad2)") (class "Default")
      (node (ref "DIGITAL_14-21") (pin "2") (pinfunction "2_2") (pintype "passive"))
    )
    (net (code "89") (name "unconnected-(DIGITAL_14-21-Pad3)") (class "Default")
      (node (ref "DIGITAL_14-21") (pin "3") (pinfunction "3_3") (pintype "passive"))
    )
    (net (code "90") (name "unconnected-(DIGITAL_14-21-Pad4)") (class "Default")
      (node (ref "DIGITAL_14-21") (pin "4") (pinfunction "4_4") (pintype "passive"))
    )
    (net (code "91") (name "unconnected-(DIGITAL_14-21-Pad5)") (class "Default")
      (node (ref "DIGITAL_14-21") (pin "5") (pinfunction "5_5") (pintype "passive"))
    )
    (net (code "92") (name "unconnected-(DIGITAL_14-21-Pad6)") (class "Default")
      (node (ref "DIGITAL_14-21") (pin "6") (pinfunction "6_6") (pintype "passive"))
    )
    (net (code "93") (name "unconnected-(IC1_2515A-CLKOUT-Pad3)") (class "Default")
      (node (ref "IC1_2515") (pin "3") (pinfunction "CLKOUT_3") (pintype "output"))
    )
    (net (code "94") (name "unconnected-(IC1_2515A-RX0BF-Pad11)") (class "Default")
      (node (ref "IC1_2515") (pin "11") (pinfunction "RX0BF_11") (pintype "output"))
    )
    (net (code "95") (name "unconnected-(IC1_2515A-RX1BF-Pad10)") (class "Default")
      (node (ref "IC1_2515") (pin "10") (pinfunction "RX1BF_10") (pintype "output"))
    )
    (net (code "96") (name "unconnected-(IC2_2551-VREF-Pad5)") (class "Default")
      (node (ref "IC2_2551") (pin "5") (pinfunction "VREF_5") (pintype "bidirectional"))
    )
    (net (code "97") (name "unconnected-(MEGA_EXPANSION-Pad9)") (class "Default")
      (node (ref "MEGA_EXPANSION") (pin "9") (pinfunction "9_9") (pintype "passive"))
    )
    (net (code "98") (name "unconnected-(MEGA_EXPANSION-Pad10)") (class "Default")
      (node (ref "MEGA_EXPANSION") (pin "10") (pinfunction "10_10") (pintype "passive"))
    )
    (net (code "99") (name "unconnected-(MEGA_EXPANSION-Pad11)") (class "Default")
      (node (ref "MEGA_EXPANSION") (pin "11") (pinfunction "11_11") (pintype "passive"))
    )
    (net (code "100") (name "unconnected-(MEGA_EXPANSION-Pad12)") (class "Default")
      (node (ref "MEGA_EXPANSION") (pin "12") (pinfunction "12_12") (pintype "passive"))
    )
    (net (code "101") (name "unconnected-(MEGA_EXPANSION-Pad13)") (class "Default")
      (node (ref "MEGA_EXPANSION") (pin "13") (pinfunction "13_13") (pintype "passive"))
    )
    (net (code "102") (name "unconnected-(MEGA_EXPANSION-Pad14)") (class "Default")
      (node (ref "MEGA_EXPANSION") (pin "14") (pinfunction "14_14") (pintype "passive"))
    )
    (net (code "103") (name "unconnected-(MEGA_EXPANSION-Pad15)") (class "Default")
      (node (ref "MEGA_EXPANSION") (pin "15") (pinfunction "15_15") (pintype "passive"))
    )
    (net (code "104") (name "unconnected-(MEGA_EXPANSION-Pad16)") (class "Default")
      (node (ref "MEGA_EXPANSION") (pin "16") (pinfunction "16_16") (pintype "passive"))
    )
    (net (code "105") (name "unconnected-(MEGA_EXPANSION-Pad21)") (class "Default")
      (node (ref "MEGA_EXPANSION") (pin "21") (pinfunction "21_21") (pintype "passive"))
    )
    (net (code "106") (name "unconnected-(MEGA_EXPANSION-Pad23)") (class "Default")
      (node (ref "MEGA_EXPANSION") (pin "23") (pinfunction "23_23") (pintype "passive"))
    )
    (net (code "107") (name "unconnected-(MEGA_EXPANSION-Pad24)") (class "Default")
      (node (ref "MEGA_EXPANSION") (pin "24") (pinfunction "24_24") (pintype "passive"))
    )
    (net (code "108") (name "unconnected-(MEGA_EXPANSION-Pad25)") (class "Default")
      (node (ref "MEGA_EXPANSION") (pin "25") (pinfunction "25_25") (pintype "passive"))
    )
    (net (code "109") (name "unconnected-(MEGA_EXPANSION-Pad26)") (class "Default")
      (node (ref "MEGA_EXPANSION") (pin "26") (pinfunction "26_26") (pintype "passive"))
    )
    (net (code "110") (name "unconnected-(MEGA_EXPANSION-Pad27)") (class "Default")
      (node (ref "MEGA_EXPANSION") (pin "27") (pinfunction "27_27") (pintype "passive"))
    )
    (net (code "111") (name "unconnected-(MEGA_EXPANSION-Pad28)") (class "Default")
      (node (ref "MEGA_EXPANSION") (pin "28") (pinfunction "28_28") (pintype "passive"))
    )
    (net (code "112") (name "unconnected-(MEGA_EXPANSION-Pad29)") (class "Default")
      (node (ref "MEGA_EXPANSION") (pin "29") (pinfunction "29_29") (pintype "passive"))
    )
    (net (code "113") (name "unconnected-(MEGA_EXPANSION-Pad30)") (class "Default")
      (node (ref "MEGA_EXPANSION") (pin "30") (pinfunction "30_30") (pintype "passive"))
    )
    (net (code "114") (name "unconnected-(MEGA_EXPANSION-Pad31)") (class "Default")
      (node (ref "MEGA_EXPANSION") (pin "31") (pinfunction "31_31") (pintype "passive"))
    )
    (net (code "115") (name "unconnected-(MEGA_EXPANSION-Pad33)") (class "Default")
      (node (ref "MEGA_EXPANSION") (pin "33") (pinfunction "33_33") (pintype "passive"))
    )
    (net (code "116") (name "unconnected-(X3-Pad13)") (class "Default")
      (node (ref "X3") (pin "13") (pinfunction "13_13") (pintype "passive"))
    )
  )
)
